# led_driver.net
KiCad netlist of a schematic drawn in EAGLE
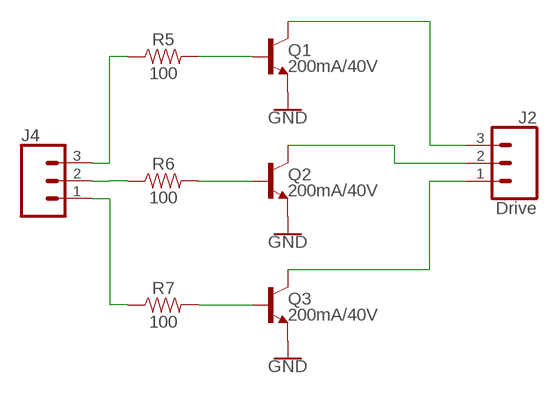
[diagram p0: schematic, sheet 1]

(export (version "E")
  (design (tool "Eeschema 10.0.6"))
  (components
    (comp (ref "J2")
      (value "Drive")
      (footprint "eagle-import:SCREWTERMINAL-5MM-3")
      (libsource (lib "eagle-import") (part "CONN_03-SCREW-5MM"))
    )
    (comp (ref "J4")
      (value "CONN_03")
      (footprint "eagle-import:1X03")
      (libsource (lib "eagle-import") (part "CONN_03"))
    )
    (comp (ref "Q1")
      (value "200mA/40V")
      (footprint "eagle-import:TO-92")
      (libsource (lib "eagle-import") (part "TRANS_NPN-2N3904"))
    )
    (comp (ref "Q2")
      (value "200mA/40V")
      (footprint "eagle-import:TO-92")
      (libsource (lib "eagle-import") (part "TRANS_NPN-2N3904"))
    )
    (comp (ref "Q3")
      (value "200mA/40V")
      (footprint "eagle-import:TO-92")
      (libsource (lib "eagle-import") (part "TRANS_NPN-2N3904"))
    )
    (comp (ref "R5")
      (value "100")
      (footprint "eagle-import:AXIAL-0.3")
      (libsource (lib "eagle-import") (part "100OHM-HORIZ-1/4W-1%"))
    )
    (comp (ref "R6")
      (value "100")
      (footprint "eagle-import:AXIAL-0.3")
      (libsource (lib "eagle-import") (part "100OHM-HORIZ-1/4W-1%"))
    )
    (comp (ref "R7")
      (value "100")
      (footprint "eagle-import:AXIAL-0.3")
      (libsource (lib "eagle-import") (part "100OHM-HORIZ-1/4W-1%"))
    )
  )
  (nets
    (net (code "1") (name "GND") (class "Default")
      (node (ref "Q1") (pin "1") (pinfunction "E_1") (pintype "passive"))
      (node (ref "Q2") (pin "1") (pinfunction "E_1") (pintype "passive"))
      (node (ref "Q3") (pin "1") (pinfunction "E_1") (pintype "passive"))
    )
    (net (code "2") (name "Net-(Q1-B)") (class "Default")
      (node (ref "Q1") (pin "2") (pinfunction "B_2") (pintype "passive"))
      (node (ref "R5") (pin "P$2") (pinfunction "2_P$2") (pintype "passive"))
    )
    (net (code "3") (name "Net-(Q1-C)") (class "Default")
      (node (ref "J2") (pin "3") (pinfunction "3_3") (pintype "passive"))
      (node (ref "Q1") (pin "3") (pinfunction "C_3") (pintype "passive"))
    )
    (net (code "4") (name "Net-(Q2-B)") (class "Default")
      (node (ref "Q2") (pin "2") (pinfunction "B_2") (pintype "passive"))
      (node (ref "R6") (pin "P$2") (pinfunction "2_P$2") (pintype "passive"))
    )
    (net (code "5") (name "Net-(Q2-C)") (class "Default")
      (node (ref "J2") (pin "2") (pinfunction "2_2") (pintype "passive"))
      (node (ref "Q2") (pin "3") (pinfunction "C_3") (pintype "passive"))
    )
    (net (code "6") (name "Net-(Q3-B)") (class "Default")
      (node (ref "Q3") (pin "2") (pinfunction "B_2") (pintype "passive"))
      (node (ref "R7") (pin "P$2") (pinfunction "2_P$2") (pintype "passive"))
    )
    (net (code "7") (name "Net-(Q3-C)") (class "Default")
      (node (ref "J2") (pin "1") (pinfunction "1_1") (pintype "passive"))
      (node (ref "Q3") (pin "3") (pinfunction "C_3") (pintype "passive"))
    )
    (net (code "8") (name "Net-(R5-1)") (class "Default")
      (node (ref "J4") (pin "3") (pinfunction "3_3") (pintype "passive"))
      (node (ref "R5") (pin "P$1") (pinfunction "1_P$1") (pintype "passive"))
    )
    (net (code "9") (name "Net-(R6-1)") (class "Default")
      (node (ref "J4") (pin "2") (pinfunction "2_2") (pintype "passive"))
      (node (ref "R6") (pin "P$1") (pinfunction "1_P$1") (pintype "passive"))
    )
    (net (code "10") (name "Net-(R7-1)") (class "Default")
      (node (ref "J4") (pin "1") (pinfunction "1_1") (pintype "passive"))
      (node (ref "R7") (pin "P$1") (pinfunction "1_P$1") (pintype "passive"))
    )
  )
)
